# power_out.net
KiCad netlist of a schematic drawn in Altium Designer
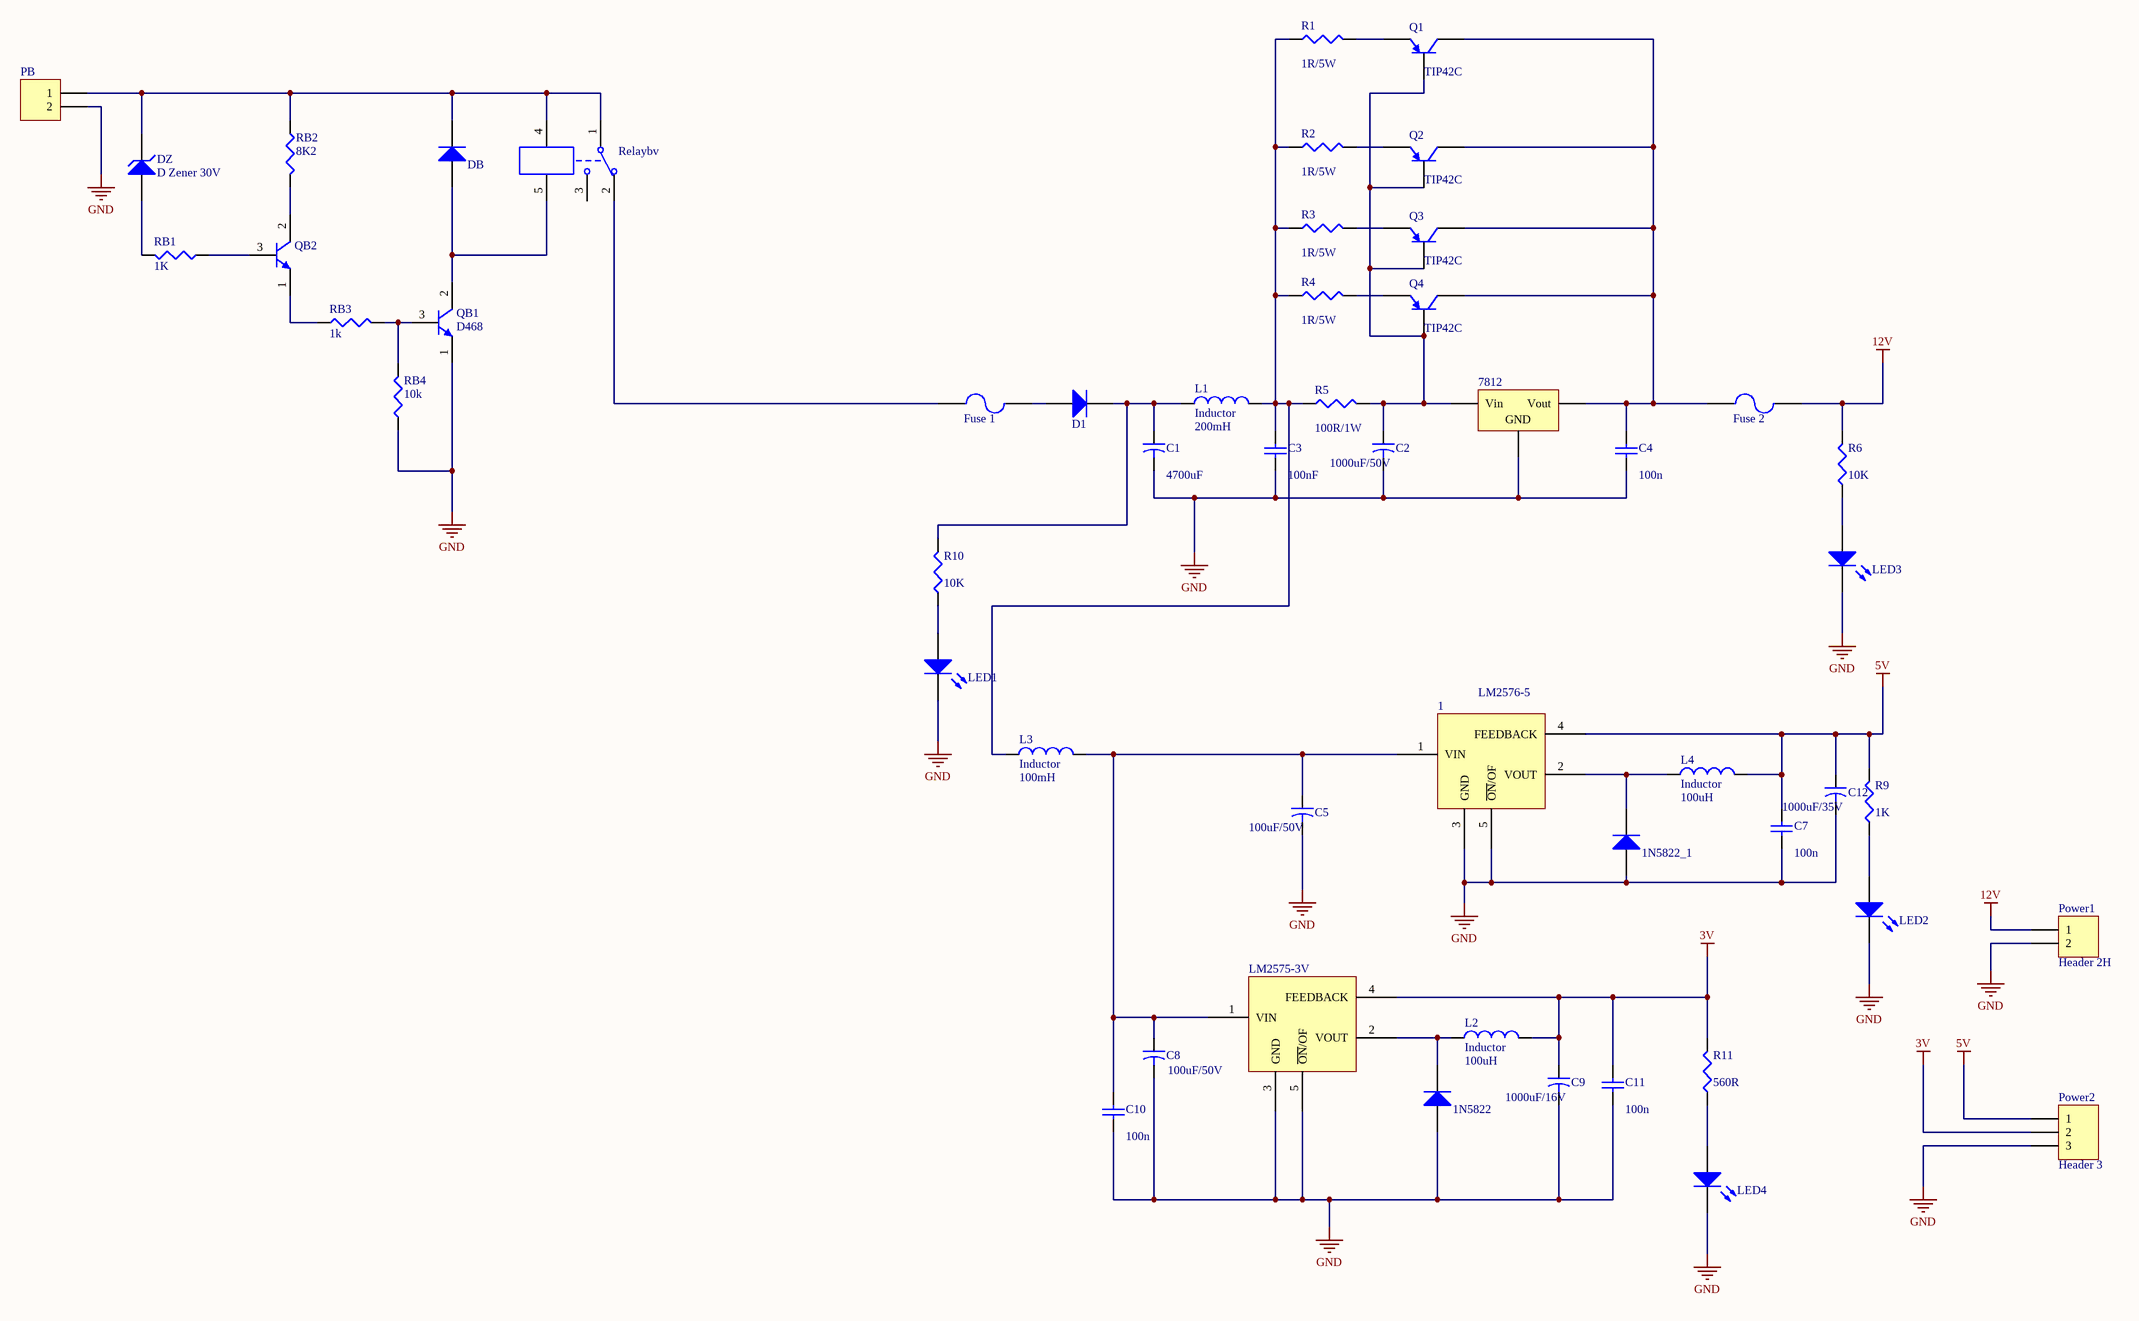
[diagram p0: power_out.SchDoc]

(export (version "E")
  (design (tool "Eeschema 10.0.6"))
  (components
    (comp (ref "1")
      (value "LM2576-5")
      (footprint "Device:LM2575_3")
      (libsource (lib "Device_Component") (part "LM2575-3V"))
    )
    (comp (ref "1N5822")
      (value "Diode")
      (footprint "Device:D_1A")
      (libsource (lib "Device_Component") (part "Diode"))
    )
    (comp (ref "1N5822_1")
      (value "Diode")
      (footprint "Device:D_1A")
      (libsource (lib "Device_Component") (part "Diode"))
    )
    (comp (ref "7812")
      (value "Volt Reg")
      (footprint "Device:78xx_NO")
      (description "Voltage Regulator")
      (fields (field (name "PUBLISHER") "Altium Limited"))
      (libsource (lib "Miscellaneous Devices") (part "Volt Reg"))
    )
    (comp (ref "C1")
      (value "4700uF")
      (footprint "Device:Tu 4700u/35V")
      (description "Capacitor")
      (fields (field (name "Comment") "Cap2") (field (name "PUBLISHER") "Altium Limited"))
      (libsource (lib "Miscellaneous Devices") (part "Cap2"))
    )
    (comp (ref "C2")
      (value "1000uF/50V")
      (footprint "Device:Tu 1000u/50V")
      (description "Capacitor")
      (fields (field (name "Comment") "Cap2") (field (name "PUBLISHER") "Altium Limited"))
      (libsource (lib "Miscellaneous Devices") (part "Cap2"))
    )
    (comp (ref "C3")
      (value "100nF")
      (footprint "Device:tu_gom")
      (description "Capacitor (Semiconductor SIM Model)")
      (fields (field (name "Comment") "Cap Semi") (field (name "PUBLISHER") "Altium Limited"))
      (libsource (lib "Miscellaneous Devices") (part "Cap Semi"))
    )
    (comp (ref "C4")
      (value "100n")
      (footprint "Device:tu_gom")
      (description "Capacitor (Semiconductor SIM Model)")
      (fields (field (name "Comment") "Cap Semi") (field (name "PUBLISHER") "Altium Limited"))
      (libsource (lib "Miscellaneous Devices") (part "Cap Semi"))
    )
    (comp (ref "C5")
      (value "100uF/50V")
      (footprint "Device:Tu 1000u/50V")
      (description "Capacitor")
      (fields (field (name "Comment") "Cap2") (field (name "PUBLISHER") "Altium Limited"))
      (libsource (lib "Miscellaneous Devices") (part "Cap2"))
    )
    (comp (ref "C7")
      (value "100n")
      (footprint "Device:tu_gom")
      (description "Capacitor (Semiconductor SIM Model)")
      (fields (field (name "Comment") "Cap Semi") (field (name "PUBLISHER") "Altium Limited"))
      (libsource (lib "Miscellaneous Devices") (part "Cap Semi"))
    )
    (comp (ref "C8")
      (value "100uF/50V")
      (footprint "Device:TU 220uF/50V")
      (description "Capacitor")
      (fields (field (name "Comment") "Cap2") (field (name "PUBLISHER") "Altium Limited"))
      (libsource (lib "Miscellaneous Devices") (part "Cap2"))
    )
    (comp (ref "C9")
      (value "1000uF/16V")
      (footprint "Device:Tu1000uF/16V")
      (description "Capacitor")
      (fields (field (name "Comment") "Cap2") (field (name "PUBLISHER") "Altium Limited"))
      (libsource (lib "Miscellaneous Devices") (part "Cap2"))
    )
    (comp (ref "C10")
      (value "100n")
      (footprint "Device:tu_gom")
      (description "Capacitor (Semiconductor SIM Model)")
      (fields (field (name "Comment") "Cap Semi") (field (name "PUBLISHER") "Altium Limited"))
      (libsource (lib "Miscellaneous Devices") (part "Cap Semi"))
    )
    (comp (ref "C11")
      (value "100n")
      (footprint "Device:tu_gom")
      (description "Capacitor (Semiconductor SIM Model)")
      (fields (field (name "Comment") "Cap Semi") (field (name "PUBLISHER") "Altium Limited"))
      (libsource (lib "Miscellaneous Devices") (part "Cap Semi"))
    )
    (comp (ref "C12")
      (value "1000uF/35V")
      (footprint "Device:Tu 1000u/35V")
      (description "Capacitor")
      (fields (field (name "Comment") "Cap2") (field (name "PUBLISHER") "Altium Limited"))
      (libsource (lib "Miscellaneous Devices") (part "Cap2"))
    )
    (comp (ref "D1")
      (value "Diode")
      (footprint "Device:D_10A")
      (libsource (lib "Device_Component") (part "Diode"))
    )
    (comp (ref "DB")
      (value "Diode")
      (footprint "Device:D_1A")
      (libsource (lib "Device_Component") (part "Diode"))
    )
    (comp (ref "DZ")
      (value "D Zener 30V")
      (footprint "Device:D_1A")
      (description "Zener Diode")
      (fields (field (name "PUBLISHER") "Altium Limited"))
      (libsource (lib "Miscellaneous Devices") (part "D Zener"))
    )
    (comp (ref "F1")
      (value "Fuse 1")
      (footprint "Device:FUSE_10A")
      (description "Fuse")
      (fields (field (name "PUBLISHER") "Altium Limited"))
      (libsource (lib "Miscellaneous Devices") (part "Fuse 2"))
    )
    (comp (ref "F2")
      (value "Fuse 2")
      (footprint "Device:FUSE_10A")
      (description "Fuse")
      (fields (field (name "PUBLISHER") "Altium Limited"))
      (libsource (lib "Miscellaneous Devices") (part "Fuse 2"))
    )
    (comp (ref "L1")
      (value "Inductor")
      (footprint "Device:Cuon cam to")
      (fields (field (name "ALTIUM_VALUE") "200mH") (field (name "PUBLISHER") "Altium Limited"))
      (libsource (lib "Miscellaneous Devices") (part "Inductor"))
    )
    (comp (ref "L2")
      (value "Inductor")
      (footprint "Device:R_Nor")
      (fields (field (name "ALTIUM_VALUE") "100uH") (field (name "PUBLISHER") "Altium Limited"))
      (libsource (lib "Miscellaneous Devices") (part "Inductor"))
    )
    (comp (ref "L3")
      (value "Inductor")
      (footprint "Device:Cuon cam nho")
      (fields (field (name "ALTIUM_VALUE") "100mH") (field (name "PUBLISHER") "Altium Limited"))
      (libsource (lib "Miscellaneous Devices") (part "Inductor"))
    )
    (comp (ref "L4")
      (value "Inductor")
      (footprint "Device:R_Nor")
      (fields (field (name "ALTIUM_VALUE") "100uH") (field (name "PUBLISHER") "Altium Limited"))
      (libsource (lib "Miscellaneous Devices") (part "Inductor"))
    )
    (comp (ref "LED1")
      (value "LED")
      (footprint "Device:LED_3")
      (libsource (lib "Device_Component") (part "LED"))
    )
    (comp (ref "LED2")
      (value "LED")
      (footprint "Device:LED_3")
      (libsource (lib "Device_Component") (part "LED"))
    )
    (comp (ref "LED3")
      (value "LED")
      (footprint "Device:LED_3")
      (libsource (lib "Device_Component") (part "LED"))
    )
    (comp (ref "LED4")
      (value "LED")
      (footprint "Device:LED_3")
      (libsource (lib "Device_Component") (part "LED"))
    )
    (comp (ref "LM2575-3V")
      (value "LM2575-xx")
      (footprint "Device:LM2575_3")
      (libsource (lib "Device_Component") (part "LM2575-3V"))
    )
    (comp (ref "PB")
      (value "Header 2")
      (footprint "Device:Coc2_20A")
      (description "Header, 2-Pin")
      (fields (field (name "PUBLISHER") "Altium Limited"))
      (libsource (lib "Miscellaneous Connectors") (part "Header 2"))
    )
    (comp (ref "Power1")
      (value "Header 2H")
      (footprint "HDR1X2H")
      (description "Header, 2-Pin, Right Angle")
      (fields (field (name "PUBLISHER") "Altium Limited"))
      (libsource (lib "Miscellaneous Connectors") (part "Header 2H"))
    )
    (comp (ref "Power2")
      (value "Header 3")
      (footprint "HDR1X3")
      (description "Header, 3-Pin")
      (fields (field (name "PUBLISHER") "Altium Limited"))
      (libsource (lib "Miscellaneous Connectors") (part "Header 3"))
    )
    (comp (ref "Q1")
      (value "TIP42C")
      (footprint "Device:TIP42C")
      (description "PNP Bipolar Transistor")
      (fields (field (name "PUBLISHER") "Altium Limited"))
      (libsource (lib "Miscellaneous Devices") (part "PNP"))
    )
    (comp (ref "Q2")
      (value "TIP42C")
      (footprint "Device:TIP42C")
      (description "PNP Bipolar Transistor")
      (fields (field (name "PUBLISHER") "Altium Limited"))
      (libsource (lib "Miscellaneous Devices") (part "PNP"))
    )
    (comp (ref "Q3")
      (value "TIP42C")
      (footprint "Device:TIP42C")
      (description "PNP Bipolar Transistor")
      (fields (field (name "PUBLISHER") "Altium Limited"))
      (libsource (lib "Miscellaneous Devices") (part "PNP"))
    )
    (comp (ref "Q4")
      (value "TIP42C")
      (footprint "Device:TIP42C")
      (description "PNP Bipolar Transistor")
      (fields (field (name "PUBLISHER") "Altium Limited"))
      (libsource (lib "Miscellaneous Devices") (part "PNP"))
    )
    (comp (ref "QB1")
      (value "D468")
      (footprint "Device:D468/A1013")
      (description "NPN Bipolar Transistor")
      (fields (field (name "PUBLISHER") "Altium Limited"))
      (libsource (lib "Miscellaneous Devices") (part "NPN"))
    )
    (comp (ref "QB2")
      (value "2N3904")
      (footprint "Device:C1815")
      (description "NPN General Purpose Amplifier")
      (fields (field (name "PUBLISHER") "Altium Limited"))
      (libsource (lib "Miscellaneous Devices") (part "2N3904"))
    )
    (comp (ref "R1")
      (value "1R/5W")
      (footprint "Device:R_CS1R/5W")
      (description "Resistor")
      (fields (field (name "Comment") "Res3") (field (name "PUBLISHER") "Altium Limited"))
      (libsource (lib "Miscellaneous Devices") (part "Res3"))
    )
    (comp (ref "R2")
      (value "1R/5W")
      (footprint "Device:R_CS1R/5W")
      (description "Resistor")
      (fields (field (name "Comment") "Res3") (field (name "PUBLISHER") "Altium Limited"))
      (libsource (lib "Miscellaneous Devices") (part "Res3"))
    )
    (comp (ref "R3")
      (value "1R/5W")
      (footprint "Device:R_CS1R/5W")
      (description "Resistor")
      (fields (field (name "Comment") "Res3") (field (name "PUBLISHER") "Altium Limited"))
      (libsource (lib "Miscellaneous Devices") (part "Res3"))
    )
    (comp (ref "R4")
      (value "1R/5W")
      (footprint "Device:R_CS1R/5W")
      (description "Resistor")
      (fields (field (name "Comment") "Res3") (field (name "PUBLISHER") "Altium Limited"))
      (libsource (lib "Miscellaneous Devices") (part "Res3"))
    )
    (comp (ref "R5")
      (value "100R/1W")
      (footprint "Device:R_Nor")
      (description "Resistor")
      (fields (field (name "Comment") "Res3") (field (name "PUBLISHER") "Altium Limited"))
      (libsource (lib "Miscellaneous Devices") (part "Res3"))
    )
    (comp (ref "R6")
      (value "10K")
      (footprint "Device:R_Nor")
      (description "Resistor")
      (fields (field (name "Comment") "Res3") (field (name "PUBLISHER") "Altium Limited"))
      (libsource (lib "Miscellaneous Devices") (part "Res3"))
    )
    (comp (ref "R9")
      (value "1K")
      (footprint "Device:R_Nor")
      (description "Resistor")
      (fields (field (name "Comment") "Res3") (field (name "PUBLISHER") "Altium Limited"))
      (libsource (lib "Miscellaneous Devices") (part "Res3"))
    )
    (comp (ref "R10")
      (value "10K")
      (footprint "Device:R_Nor")
      (description "Resistor")
      (fields (field (name "Comment") "Res3") (field (name "PUBLISHER") "Altium Limited"))
      (libsource (lib "Miscellaneous Devices") (part "Res3"))
    )
    (comp (ref "R11")
      (value "560R")
      (footprint "Device:R_Nor")
      (description "Resistor")
      (fields (field (name "Comment") "Res3") (field (name "PUBLISHER") "Altium Limited"))
      (libsource (lib "Miscellaneous Devices") (part "Res3"))
    )
    (comp (ref "RB1")
      (value "1K")
      (footprint "Device:R_Nor")
      (description "Resistor")
      (fields (field (name "Comment") "Res3") (field (name "PUBLISHER") "Altium Limited"))
      (libsource (lib "Miscellaneous Devices") (part "Res3"))
    )
    (comp (ref "RB2")
      (value "8K2")
      (footprint "Device:R_Nor")
      (description "Resistor")
      (fields (field (name "Comment") "Res3") (field (name "PUBLISHER") "Altium Limited"))
      (libsource (lib "Miscellaneous Devices") (part "Res3"))
    )
    (comp (ref "RB3")
      (value "1k")
      (footprint "Device:R_Nor")
      (description "Resistor")
      (fields (field (name "Comment") "Res3") (field (name "PUBLISHER") "Altium Limited"))
      (libsource (lib "Miscellaneous Devices") (part "Res3"))
    )
    (comp (ref "RB4")
      (value "10k")
      (footprint "Device:R_Nor")
      (description "Resistor")
      (fields (field (name "Comment") "Res3") (field (name "PUBLISHER") "Altium Limited"))
      (libsource (lib "Miscellaneous Devices") (part "Res3"))
    )
    (comp (ref "Relaybv")
      (value "Relay-SPDT")
      (footprint "Device:Role 12V")
      (description "Single-Pole Dual-Throw Relay")
      (fields (field (name "PUBLISHER") "Altium Limited"))
      (libsource (lib "Miscellaneous Devices") (part "Relay-SPDT"))
    )
  )
  (nets
    (net (code "1") (name "3V") (class "Default")
      (node (ref "C11") (pin "2") (pinfunction "2_2") (pintype "passive"))
      (node (ref "C9") (pin "1") (pinfunction "1_1") (pintype "passive"))
      (node (ref "L2") (pin "2") (pinfunction "2_2") (pintype "passive"))
      (node (ref "LM2575-3V") (pin "4") (pinfunction "FEEDBACK_4") (pintype "passive"))
      (node (ref "Power2") (pin "2") (pinfunction "2_2") (pintype "passive"))
      (node (ref "R11") (pin "2") (pinfunction "2_2") (pintype "passive"))
    )
    (net (code "2") (name "5V") (class "Default")
      (node (ref "1") (pin "4") (pinfunction "FEEDBACK_4") (pintype "passive"))
      (node (ref "C12") (pin "1") (pinfunction "1_1") (pintype "passive"))
      (node (ref "C7") (pin "2") (pinfunction "2_2") (pintype "passive"))
      (node (ref "L4") (pin "2") (pinfunction "2_2") (pintype "passive"))
      (node (ref "Power2") (pin "1") (pinfunction "1_1") (pintype "passive"))
      (node (ref "R9") (pin "2") (pinfunction "2_2") (pintype "passive"))
    )
    (net (code "3") (name "12V") (class "Default")
      (node (ref "F2") (pin "2") (pinfunction "2_2") (pintype "passive"))
      (node (ref "Power1") (pin "1") (pinfunction "1_1") (pintype "passive"))
      (node (ref "R6") (pin "2") (pinfunction "2_2") (pintype "passive"))
    )
    (net (code "4") (name "GND") (class "Default")
      (node (ref "1") (pin "3") (pinfunction "GND_3") (pintype "passive"))
      (node (ref "1") (pin "5") (pinfunction "~{ON}/OF_5") (pintype "passive"))
      (node (ref "1N5822") (pin "1") (pinfunction "A_1") (pintype "passive"))
      (node (ref "1N5822_1") (pin "1") (pinfunction "A_1") (pintype "passive"))
      (node (ref "7812") (pin "2") (pinfunction "GND_2") (pintype "passive"))
      (node (ref "C1") (pin "2") (pinfunction "2_2") (pintype "passive"))
      (node (ref "C10") (pin "1") (pinfunction "1_1") (pintype "passive"))
      (node (ref "C11") (pin "1") (pinfunction "1_1") (pintype "passive"))
      (node (ref "C12") (pin "2") (pinfunction "2_2") (pintype "passive"))
      (node (ref "C2") (pin "2") (pinfunction "2_2") (pintype "passive"))
      (node (ref "C3") (pin "1") (pinfunction "1_1") (pintype "passive"))
      (node (ref "C4") (pin "1") (pinfunction "1_1") (pintype "passive"))
      (node (ref "C5") (pin "2") (pinfunction "2_2") (pintype "passive"))
      (node (ref "C7") (pin "1") (pinfunction "1_1") (pintype "passive"))
      (node (ref "C8") (pin "2") (pinfunction "2_2") (pintype "passive"))
      (node (ref "C9") (pin "2") (pinfunction "2_2") (pintype "passive"))
      (node (ref "LED1") (pin "2") (pinfunction "K_2") (pintype "passive"))
      (node (ref "LED2") (pin "2") (pinfunction "K_2") (pintype "passive"))
      (node (ref "LED3") (pin "2") (pinfunction "K_2") (pintype "passive"))
      (node (ref "LED4") (pin "2") (pinfunction "K_2") (pintype "passive"))
      (node (ref "LM2575-3V") (pin "3") (pinfunction "GND_3") (pintype "passive"))
      (node (ref "LM2575-3V") (pin "5") (pinfunction "~{ON}/OF_5") (pintype "passive"))
      (node (ref "PB") (pin "2") (pinfunction "2_2") (pintype "passive"))
      (node (ref "Power1") (pin "2") (pinfunction "2_2") (pintype "passive"))
      (node (ref "Power2") (pin "3") (pinfunction "3_3") (pintype "passive"))
      (node (ref "QB1") (pin "1") (pinfunction "E_1") (pintype "passive"))
      (node (ref "RB4") (pin "1") (pinfunction "1_1") (pintype "passive"))
    )
    (net (code "5") (name "Net-(1-VIN)") (class "Default")
      (node (ref "1") (pin "1") (pinfunction "VIN_1") (pintype "passive"))
      (node (ref "C10") (pin "2") (pinfunction "2_2") (pintype "passive"))
      (node (ref "C5") (pin "1") (pinfunction "1_1") (pintype "passive"))
      (node (ref "C8") (pin "1") (pinfunction "1_1") (pintype "passive"))
      (node (ref "L3") (pin "2") (pinfunction "2_2") (pintype "passive"))
      (node (ref "LM2575-3V") (pin "1") (pinfunction "VIN_1") (pintype "passive"))
    )
    (net (code "6") (name "Net-(1-VOUT)") (class "Default")
      (node (ref "1") (pin "2") (pinfunction "VOUT_2") (pintype "passive"))
      (node (ref "1N5822_1") (pin "2") (pinfunction "K_2") (pintype "passive"))
      (node (ref "L4") (pin "1") (pinfunction "1_1") (pintype "passive"))
    )
    (net (code "7") (name "Net-(1N5822-K)") (class "Default")
      (node (ref "1N5822") (pin "2") (pinfunction "K_2") (pintype "passive"))
      (node (ref "L2") (pin "1") (pinfunction "1_1") (pintype "passive"))
      (node (ref "LM2575-3V") (pin "2") (pinfunction "VOUT_2") (pintype "passive"))
    )
    (net (code "8") (name "Net-(7812-Vin)") (class "Default")
      (node (ref "7812") (pin "1") (pinfunction "Vin_1") (pintype "passive"))
      (node (ref "C2") (pin "1") (pinfunction "1_1") (pintype "passive"))
      (node (ref "Q1") (pin "1") (pinfunction "B_1") (pintype "passive"))
      (node (ref "Q2") (pin "1") (pinfunction "B_1") (pintype "passive"))
      (node (ref "Q3") (pin "1") (pinfunction "B_1") (pintype "passive"))
      (node (ref "Q4") (pin "1") (pinfunction "B_1") (pintype "passive"))
      (node (ref "R5") (pin "2") (pinfunction "2_2") (pintype "passive"))
    )
    (net (code "9") (name "Net-(7812-Vout)") (class "Default")
      (node (ref "7812") (pin "3") (pinfunction "Vout_3") (pintype "passive"))
      (node (ref "C4") (pin "2") (pinfunction "2_2") (pintype "passive"))
      (node (ref "F2") (pin "1") (pinfunction "1_1") (pintype "passive"))
      (node (ref "Q1") (pin "2") (pinfunction "C_2") (pintype "passive"))
      (node (ref "Q2") (pin "2") (pinfunction "C_2") (pintype "passive"))
      (node (ref "Q3") (pin "2") (pinfunction "C_2") (pintype "passive"))
      (node (ref "Q4") (pin "2") (pinfunction "C_2") (pintype "passive"))
    )
    (net (code "10") (name "Net-(C3-Pad2)") (class "Default")
      (node (ref "C3") (pin "2") (pinfunction "2_2") (pintype "passive"))
      (node (ref "L1") (pin "2") (pinfunction "2_2") (pintype "passive"))
      (node (ref "L3") (pin "1") (pinfunction "1_1") (pintype "passive"))
      (node (ref "R1") (pin "1") (pinfunction "1_1") (pintype "passive"))
      (node (ref "R2") (pin "1") (pinfunction "1_1") (pintype "passive"))
      (node (ref "R3") (pin "1") (pinfunction "1_1") (pintype "passive"))
      (node (ref "R4") (pin "1") (pinfunction "1_1") (pintype "passive"))
      (node (ref "R5") (pin "1") (pinfunction "1_1") (pintype "passive"))
    )
    (net (code "11") (name "Net-(D1-A)") (class "Default")
      (node (ref "D1") (pin "1") (pinfunction "A_1") (pintype "passive"))
      (node (ref "F1") (pin "2") (pinfunction "2_2") (pintype "passive"))
    )
    (net (code "12") (name "Net-(D1-K)") (class "Default")
      (node (ref "C1") (pin "1") (pinfunction "1_1") (pintype "passive"))
      (node (ref "D1") (pin "2") (pinfunction "K_2") (pintype "passive"))
      (node (ref "L1") (pin "1") (pinfunction "1_1") (pintype "passive"))
      (node (ref "R10") (pin "2") (pinfunction "2_2") (pintype "passive"))
    )
    (net (code "13") (name "Net-(DB-A)") (class "Default")
      (node (ref "DB") (pin "1") (pinfunction "A_1") (pintype "passive"))
      (node (ref "QB1") (pin "2") (pinfunction "C_2") (pintype "passive"))
      (node (ref "Relaybv") (pin "5") (pinfunction "5_5") (pintype "passive"))
    )
    (net (code "14") (name "Net-(DB-K)") (class "Default")
      (node (ref "DB") (pin "2") (pinfunction "K_2") (pintype "passive"))
      (node (ref "DZ") (pin "2") (pinfunction "K_2") (pintype "passive"))
      (node (ref "PB") (pin "1") (pinfunction "1_1") (pintype "passive"))
      (node (ref "RB2") (pin "1") (pinfunction "1_1") (pintype "passive"))
      (node (ref "Relaybv") (pin "1") (pinfunction "1_1") (pintype "passive"))
      (node (ref "Relaybv") (pin "4") (pinfunction "4_4") (pintype "passive"))
    )
    (net (code "15") (name "Net-(DZ-A)") (class "Default")
      (node (ref "DZ") (pin "1") (pinfunction "A_1") (pintype "passive"))
      (node (ref "RB1") (pin "2") (pinfunction "2_2") (pintype "passive"))
    )
    (net (code "16") (name "Net-(F1-Pad1)") (class "Default")
      (node (ref "F1") (pin "1") (pinfunction "1_1") (pintype "passive"))
      (node (ref "Relaybv") (pin "2") (pinfunction "2_2") (pintype "passive"))
    )
    (net (code "17") (name "Net-(LED1-A)") (class "Default")
      (node (ref "LED1") (pin "1") (pinfunction "A_1") (pintype "passive"))
      (node (ref "R10") (pin "1") (pinfunction "1_1") (pintype "passive"))
    )
    (net (code "18") (name "Net-(LED2-A)") (class "Default")
      (node (ref "LED2") (pin "1") (pinfunction "A_1") (pintype "passive"))
      (node (ref "R9") (pin "1") (pinfunction "1_1") (pintype "passive"))
    )
    (net (code "19") (name "Net-(LED3-A)") (class "Default")
      (node (ref "LED3") (pin "1") (pinfunction "A_1") (pintype "passive"))
      (node (ref "R6") (pin "1") (pinfunction "1_1") (pintype "passive"))
    )
    (net (code "20") (name "Net-(LED4-A)") (class "Default")
      (node (ref "LED4") (pin "1") (pinfunction "A_1") (pintype "passive"))
      (node (ref "R11") (pin "1") (pinfunction "1_1") (pintype "passive"))
    )
    (net (code "21") (name "Net-(Q1-E)") (class "Default")
      (node (ref "Q1") (pin "3") (pinfunction "E_3") (pintype "passive"))
      (node (ref "R1") (pin "2") (pinfunction "2_2") (pintype "passive"))
    )
    (net (code "22") (name "Net-(Q2-E)") (class "Default")
      (node (ref "Q2") (pin "3") (pinfunction "E_3") (pintype "passive"))
      (node (ref "R2") (pin "2") (pinfunction "2_2") (pintype "passive"))
    )
    (net (code "23") (name "Net-(Q3-E)") (class "Default")
      (node (ref "Q3") (pin "3") (pinfunction "E_3") (pintype "passive"))
      (node (ref "R3") (pin "2") (pinfunction "2_2") (pintype "passive"))
    )
    (net (code "24") (name "Net-(Q4-E)") (class "Default")
      (node (ref "Q4") (pin "3") (pinfunction "E_3") (pintype "passive"))
      (node (ref "R4") (pin "2") (pinfunction "2_2") (pintype "passive"))
    )
    (net (code "25") (name "Net-(QB1-B)") (class "Default")
      (node (ref "QB1") (pin "3") (pinfunction "B_3") (pintype "passive"))
      (node (ref "RB3") (pin "2") (pinfunction "2_2") (pintype "passive"))
      (node (ref "RB4") (pin "2") (pinfunction "2_2") (pintype "passive"))
    )
    (net (code "26") (name "Net-(QB2-B)") (class "Default")
      (node (ref "QB2") (pin "3") (pinfunction "B_3") (pintype "passive"))
      (node (ref "RB1") (pin "1") (pinfunction "1_1") (pintype "passive"))
    )
    (net (code "27") (name "Net-(QB2-C)") (class "Default")
      (node (ref "QB2") (pin "2") (pinfunction "C_2") (pintype "passive"))
      (node (ref "RB2") (pin "2") (pinfunction "2_2") (pintype "passive"))
    )
    (net (code "28") (name "Net-(QB2-E)") (class "Default")
      (node (ref "QB2") (pin "1") (pinfunction "E_1") (pintype "passive"))
      (node (ref "RB3") (pin "1") (pinfunction "1_1") (pintype "passive"))
    )
    (net (code "29") (name "unconnected-(Relaybv-Pad3)") (class "Default")
      (node (ref "Relaybv") (pin "3") (pinfunction "3_3") (pintype "passive"))
    )
  )
)
